# Ethernet.net
KiCad netlist of a schematic drawn in Altium Designer
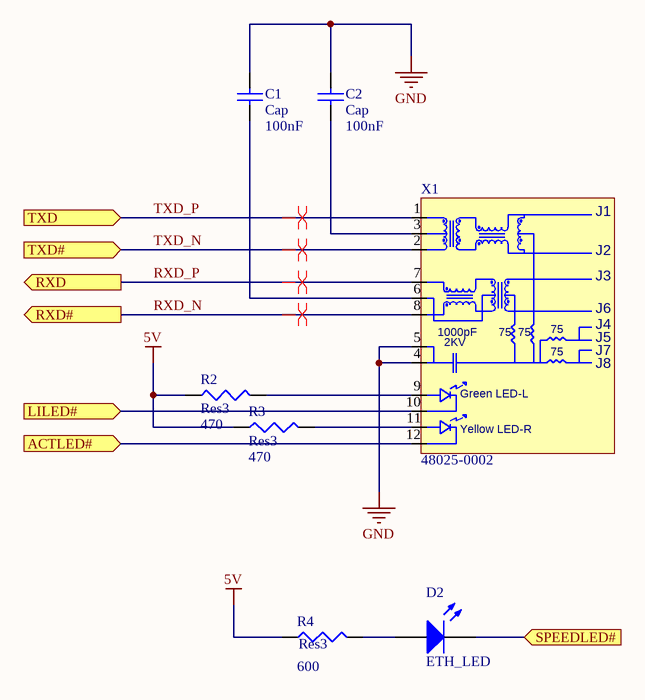
[diagram p0: Ethernet.SchDoc]

(export (version "E")
  (design (tool "Eeschema 10.0.6"))
  (components
    (comp (ref "C1")
      (value "Cap")
      (footprint "0603")
      (description "Capacitor")
      (fields (field (name "ALTIUM_VALUE") "100nF") (field (name "PUBLISHER") "Altium Limited"))
      (libsource (lib "Miscellaneous Devices") (part "Cap"))
    )
    (comp (ref "C2")
      (value "Cap")
      (footprint "0603")
      (description "Capacitor")
      (fields (field (name "ALTIUM_VALUE") "100nF") (field (name "PUBLISHER") "Altium Limited"))
      (libsource (lib "Miscellaneous Devices") (part "Cap"))
    )
    (comp (ref "D2")
      (value "ETH_LED")
      (footprint "0805")
      (description "Typical RED GaAs LED")
      (fields (field (name "PUBLISHER") "Altium Limited"))
      (libsource (lib "Miscellaneous Devices") (part "LED1"))
    )
    (comp (ref "R2")
      (value "Res3")
      (footprint "J1-0603")
      (description "Resistor")
      (fields (field (name "ALTIUM_VALUE") "470") (field (name "PUBLISHER") "Altium Limited"))
      (libsource (lib "Miscellaneous Devices") (part "Res3"))
    )
    (comp (ref "R3")
      (value "Res3")
      (footprint "J1-0603")
      (description "Resistor")
      (fields (field (name "ALTIUM_VALUE") "470") (field (name "PUBLISHER") "Altium Limited"))
      (libsource (lib "Miscellaneous Devices") (part "Res3"))
    )
    (comp (ref "R4")
      (value "Res3")
      (footprint "J1-0603")
      (description "Resistor")
      (fields (field (name "ALTIUM_VALUE") "600") (field (name "PUBLISHER") "Altium Limited"))
      (libsource (lib "Miscellaneous Devices") (part "Res3"))
    )
    (comp (ref "X1")
      (value "48025-0002")
      (footprint "48025-0002")
      (description "Modular RJ45 Jack w/ Magnetics & LEDs")
      (libsource (lib "MolexModularJacks") (part "48025-0002"))
    )
  )
  (nets
    (net (code "1") (name "/ACTLED#") (class "Default")
      (node (ref "X1") (pin "12") (pinfunction "12_12") (pintype "passive"))
    )
    (net (code "2") (name "/LILED#") (class "Default")
      (node (ref "X1") (pin "10") (pinfunction "10_10") (pintype "passive"))
    )
    (net (code "3") (name "/RXD_N") (class "Default")
      (node (ref "X1") (pin "8") (pinfunction "8_8") (pintype "passive"))
    )
    (net (code "4") (name "/RXD_P") (class "Default")
      (node (ref "X1") (pin "7") (pinfunction "7_7") (pintype "passive"))
    )
    (net (code "5") (name "/SPEEDLED#") (class "Default")
      (node (ref "D2") (pin "2") (pinfunction "K_2") (pintype "passive"))
    )
    (net (code "6") (name "/TXD_N") (class "Default")
      (node (ref "X1") (pin "2") (pinfunction "2_2") (pintype "passive"))
    )
    (net (code "7") (name "/TXD_P") (class "Default")
      (node (ref "X1") (pin "1") (pinfunction "1_1") (pintype "passive"))
    )
    (net (code "8") (name "5V") (class "Default")
      (node (ref "R2") (pin "1") (pinfunction "1_1") (pintype "passive"))
      (node (ref "R3") (pin "1") (pinfunction "1_1") (pintype "passive"))
      (node (ref "R4") (pin "1") (pinfunction "1_1") (pintype "passive"))
    )
    (net (code "9") (name "GND") (class "Default")
      (node (ref "C1") (pin "2") (pinfunction "2_2") (pintype "passive"))
      (node (ref "C2") (pin "2") (pinfunction "2_2") (pintype "passive"))
      (node (ref "X1") (pin "4") (pinfunction "4_4") (pintype "passive"))
      (node (ref "X1") (pin "5") (pinfunction "5_5") (pintype "passive"))
    )
    (net (code "10") (name "Net-(C1-Pad1)") (class "Default")
      (node (ref "C1") (pin "1") (pinfunction "1_1") (pintype "passive"))
      (node (ref "X1") (pin "6") (pinfunction "6_6") (pintype "passive"))
    )
    (net (code "11") (name "Net-(C2-Pad1)") (class "Default")
      (node (ref "C2") (pin "1") (pinfunction "1_1") (pintype "passive"))
      (node (ref "X1") (pin "3") (pinfunction "3_3") (pintype "passive"))
    )
    (net (code "12") (name "Net-(D2-A)") (class "Default")
      (node (ref "D2") (pin "1") (pinfunction "A_1") (pintype "passive"))
      (node (ref "R4") (pin "2") (pinfunction "2_2") (pintype "passive"))
    )
    (net (code "13") (name "Net-(R2-Pad2)") (class "Default")
      (node (ref "R2") (pin "2") (pinfunction "2_2") (pintype "passive"))
      (node (ref "X1") (pin "9") (pinfunction "9_9") (pintype "passive"))
    )
    (net (code "14") (name "Net-(R3-Pad2)") (class "Default")
      (node (ref "R3") (pin "2") (pinfunction "2_2") (pintype "passive"))
      (node (ref "X1") (pin "11") (pinfunction "11_11") (pintype "passive"))
    )
  )
)
